# Power.net
KiCad netlist of a schematic drawn in Altium Designer
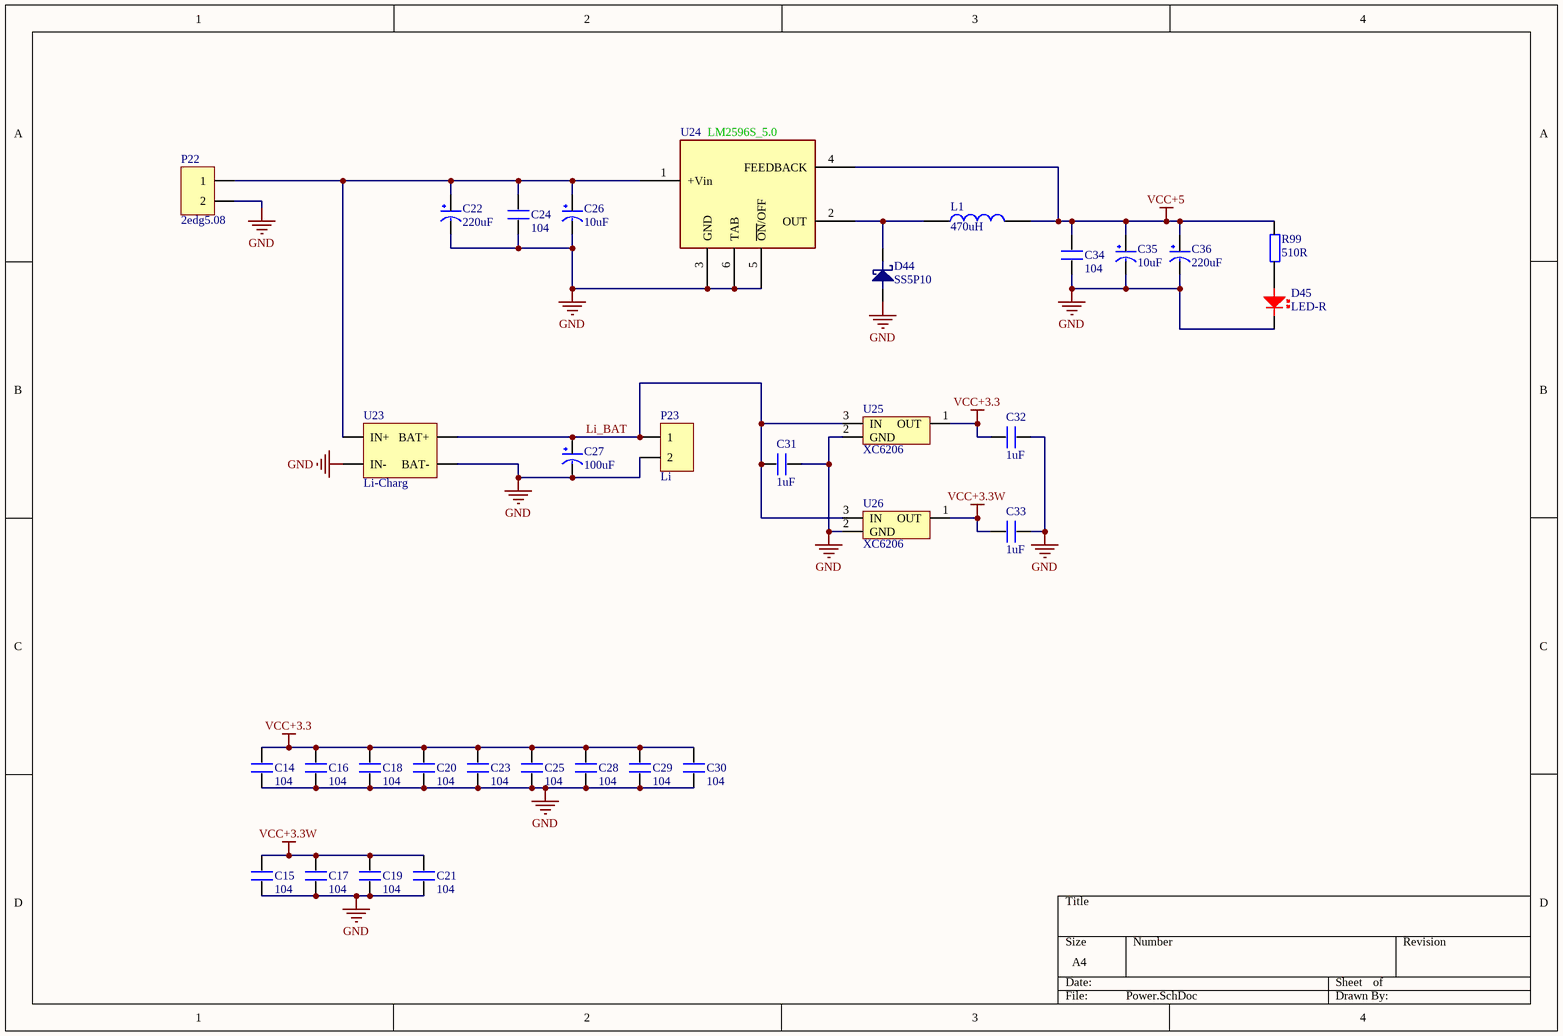
[diagram p0: Power.SchDoc]

(export (version "E")
  (design (tool "Eeschema 10.0.6"))
  (components
    (comp (ref "C14") (value "104") (footprint "0805-CAP") (libsource (lib "mylib") (part "C")))
    (comp (ref "C15") (value "104") (footprint "0805-CAP") (libsource (lib "mylib") (part "C")))
    (comp (ref "C16") (value "104") (footprint "0805-CAP") (libsource (lib "mylib") (part "C")))
    (comp (ref "C17") (value "104") (footprint "0805-CAP") (libsource (lib "mylib") (part "C")))
    (comp (ref "C18") (value "104") (footprint "0805-CAP") (libsource (lib "mylib") (part "C")))
    (comp (ref "C19") (value "104") (footprint "0805-CAP") (libsource (lib "mylib") (part "C")))
    (comp (ref "C20") (value "104") (footprint "0805-CAP") (libsource (lib "mylib") (part "C")))
    (comp (ref "C21") (value "104") (footprint "0805-CAP") (libsource (lib "mylib") (part "C")))
    (comp (ref "C22") (value "220uF") (footprint "CAP3.0") (libsource (lib "mylib") (part "CAP")))
    (comp (ref "C23") (value "104") (footprint "0805-CAP") (libsource (lib "mylib") (part "C")))
    (comp (ref "C24") (value "104") (footprint "0805-CAP") (libsource (lib "mylib") (part "C")))
    (comp (ref "C25") (value "104") (footprint "0805-CAP") (libsource (lib "mylib") (part "C")))
    (comp (ref "C26") (value "10uF") (footprint "CAP3.0") (libsource (lib "mylib") (part "CAP")))
    (comp (ref "C27") (value "100uF") (footprint "CAP2.54") (libsource (lib "mylib") (part "CAP")))
    (comp (ref "C28") (value "104") (footprint "0805-CAP") (libsource (lib "mylib") (part "C")))
    (comp (ref "C29") (value "104") (footprint "0805-CAP") (libsource (lib "mylib") (part "C")))
    (comp (ref "C30") (value "104") (footprint "0805-CAP") (libsource (lib "mylib") (part "C")))
    (comp (ref "C31") (value "1uF") (footprint "0805-CAP") (libsource (lib "mylib") (part "C")))
    (comp (ref "C32") (value "1uF") (footprint "0805-CAP") (libsource (lib "mylib") (part "C")))
    (comp (ref "C33") (value "1uF") (footprint "0805-CAP") (libsource (lib "mylib") (part "C")))
    (comp (ref "C34") (value "104") (footprint "0805-CAP") (libsource (lib "mylib") (part "C")))
    (comp (ref "C35") (value "10uF") (footprint "CAP3.0") (libsource (lib "mylib") (part "CAP")))
    (comp (ref "C36") (value "220uF") (footprint "CAP3.0") (libsource (lib "mylib") (part "CAP")))
    (comp (ref "D44")
      (value "SS5P10")
      (footprint "TO-277A")
      (description "肖特基二极管")
      (libsource (lib "mylib") (part "SS5P10"))
    )
    (comp (ref "D45")
      (value "LED-R")
      (footprint "DIO-LIG")
      (description "红色LED")
      (libsource (lib "mylib") (part "LED-RED"))
    )
    (comp (ref "L1") (value "470uH") (footprint "MSS1278CUST") (libsource (lib "mylib") (part "INDUCTOR")))
    (comp (ref "P22")
      (value "2edg5.08")
      (footprint "2edg5.08_2")
      (description "端子")
      (libsource (lib "") (part "2EDG5.08_2_1"))
    )
    (comp (ref "P23")
      (value "Li")
      (footprint "2edg5.08_2")
      (description "端子")
      (libsource (lib "mylib") (part "2EDG5.08_2"))
    )
    (comp (ref "R99") (value "510R") (footprint "0805-RES") (libsource (lib "mylib") (part "Res")))
    (comp (ref "U23")
      (value "Li-Charg")
      (footprint "Li-Charg")
      (description "锂电池充电模块")
      (libsource (lib "mylib") (part "Li-Charg"))
    )
    (comp (ref "U24")
      (value "LM2596S_5.0")
      (footprint "TO-263-5-2")
      (description "3A开关电源芯片")
      (libsource (lib "Zhuangzaiji") (part "LM2596S_5.0"))
    )
    (comp (ref "U25")
      (value "XC6206")
      (footprint "SOT-23R")
      (description "LDO")
      (libsource (lib "mylib") (part "XC6206"))
    )
    (comp (ref "U26")
      (value "XC6206")
      (footprint "SOT-23R")
      (description "LDO")
      (libsource (lib "mylib") (part "XC6206"))
    )
  )
  (nets
    (net (code "1") (name "/Li_BAT") (class "Default")
      (node (ref "C27") (pin "1") (pinfunction "VCC_1") (pintype "passive"))
      (node (ref "C31") (pin "1") (pintype "passive"))
      (node (ref "P23") (pin "1") (pinfunction "1_1") (pintype "passive"))
      (node (ref "U23") (pin "4") (pinfunction "BAT+_4") (pintype "passive"))
      (node (ref "U25") (pin "3") (pinfunction "IN_3") (pintype "passive"))
      (node (ref "U26") (pin "3") (pinfunction "IN_3") (pintype "passive"))
    )
    (net (code "2") (name "GND") (class "Default")
      (node (ref "C14") (pin "1") (pintype "passive"))
      (node (ref "C15") (pin "1") (pintype "passive"))
      (node (ref "C16") (pin "1") (pintype "passive"))
      (node (ref "C17") (pin "1") (pintype "passive"))
      (node (ref "C18") (pin "1") (pintype "passive"))
      (node (ref "C19") (pin "1") (pintype "passive"))
      (node (ref "C20") (pin "1") (pintype "passive"))
      (node (ref "C21") (pin "1") (pintype "passive"))
      (node (ref "C22") (pin "2") (pinfunction "GND_2") (pintype "passive"))
      (node (ref "C23") (pin "1") (pintype "passive"))
      (node (ref "C24") (pin "1") (pintype "passive"))
      (node (ref "C25") (pin "1") (pintype "passive"))
      (node (ref "C26") (pin "2") (pinfunction "GND_2") (pintype "passive"))
      (node (ref "C27") (pin "2") (pinfunction "GND_2") (pintype "passive"))
      (node (ref "C28") (pin "1") (pintype "passive"))
      (node (ref "C29") (pin "1") (pintype "passive"))
      (node (ref "C30") (pin "1") (pintype "passive"))
      (node (ref "C31") (pin "2") (pintype "passive"))
      (node (ref "C32") (pin "2") (pintype "passive"))
      (node (ref "C33") (pin "2") (pintype "passive"))
      (node (ref "C34") (pin "1") (pintype "passive"))
      (node (ref "C35") (pin "2") (pinfunction "GND_2") (pintype "passive"))
      (node (ref "C36") (pin "2") (pinfunction "GND_2") (pintype "passive"))
      (node (ref "D44") (pin "1") (pintype "passive"))
      (node (ref "D45") (pin "2") (pintype "passive"))
      (node (ref "P22") (pin "2") (pinfunction "2_2") (pintype "passive"))
      (node (ref "P23") (pin "2") (pinfunction "2_2") (pintype "passive"))
      (node (ref "U23") (pin "2") (pinfunction "IN-_2") (pintype "passive"))
      (node (ref "U23") (pin "3") (pinfunction "BAT-_3") (pintype "passive"))
      (node (ref "U24") (pin "3") (pinfunction "GND_3") (pintype "passive"))
      (node (ref "U24") (pin "5") (pinfunction "~{ON}/OFF_5") (pintype "passive"))
      (node (ref "U24") (pin "6") (pinfunction "TAB_6") (pintype "passive"))
      (node (ref "U25") (pin "2") (pinfunction "GND_2") (pintype "passive"))
      (node (ref "U26") (pin "2") (pinfunction "GND_2") (pintype "passive"))
    )
    (net (code "3") (name "Net-(C22-VCC)") (class "Default")
      (node (ref "C22") (pin "1") (pinfunction "VCC_1") (pintype "passive"))
      (node (ref "C24") (pin "2") (pintype "passive"))
      (node (ref "C26") (pin "1") (pinfunction "VCC_1") (pintype "passive"))
      (node (ref "P22") (pin "1") (pinfunction "1_1") (pintype "passive"))
      (node (ref "U23") (pin "1") (pinfunction "IN+_1") (pintype "passive"))
      (node (ref "U24") (pin "1") (pinfunction "+Vin_1") (pintype "passive"))
    )
    (net (code "4") (name "Net-(D45-Pad1)") (class "Default")
      (node (ref "D45") (pin "1") (pintype "passive"))
      (node (ref "R99") (pin "1") (pintype "passive"))
    )
    (net (code "5") (name "Net-(U24-OUT)") (class "Default")
      (node (ref "D44") (pin "2") (pintype "passive"))
      (node (ref "L1") (pin "1") (pinfunction "1_1") (pintype "passive"))
      (node (ref "U24") (pin "2") (pinfunction "OUT_2") (pintype "passive"))
    )
    (net (code "6") (name "VCC+3.3") (class "Default")
      (node (ref "C14") (pin "2") (pintype "passive"))
      (node (ref "C16") (pin "2") (pintype "passive"))
      (node (ref "C18") (pin "2") (pintype "passive"))
      (node (ref "C20") (pin "2") (pintype "passive"))
      (node (ref "C23") (pin "2") (pintype "passive"))
      (node (ref "C25") (pin "2") (pintype "passive"))
      (node (ref "C28") (pin "2") (pintype "passive"))
      (node (ref "C29") (pin "2") (pintype "passive"))
      (node (ref "C30") (pin "2") (pintype "passive"))
      (node (ref "C32") (pin "1") (pintype "passive"))
      (node (ref "U25") (pin "1") (pinfunction "OUT_1") (pintype "passive"))
    )
    (net (code "7") (name "VCC+3.3W") (class "Default")
      (node (ref "C15") (pin "2") (pintype "passive"))
      (node (ref "C17") (pin "2") (pintype "passive"))
      (node (ref "C19") (pin "2") (pintype "passive"))
      (node (ref "C21") (pin "2") (pintype "passive"))
      (node (ref "C33") (pin "1") (pintype "passive"))
      (node (ref "U26") (pin "1") (pinfunction "OUT_1") (pintype "passive"))
    )
    (net (code "8") (name "VCC+5") (class "Default")
      (node (ref "C34") (pin "2") (pintype "passive"))
      (node (ref "C35") (pin "1") (pinfunction "VCC_1") (pintype "passive"))
      (node (ref "C36") (pin "1") (pinfunction "VCC_1") (pintype "passive"))
      (node (ref "L1") (pin "2") (pinfunction "2_2") (pintype "passive"))
      (node (ref "R99") (pin "2") (pintype "passive"))
      (node (ref "U24") (pin "4") (pinfunction "FEEDBACK_4") (pintype "passive"))
    )
  )
)
